# lcd_booster_mk4.net
KiCad netlist of a schematic drawn in EAGLE
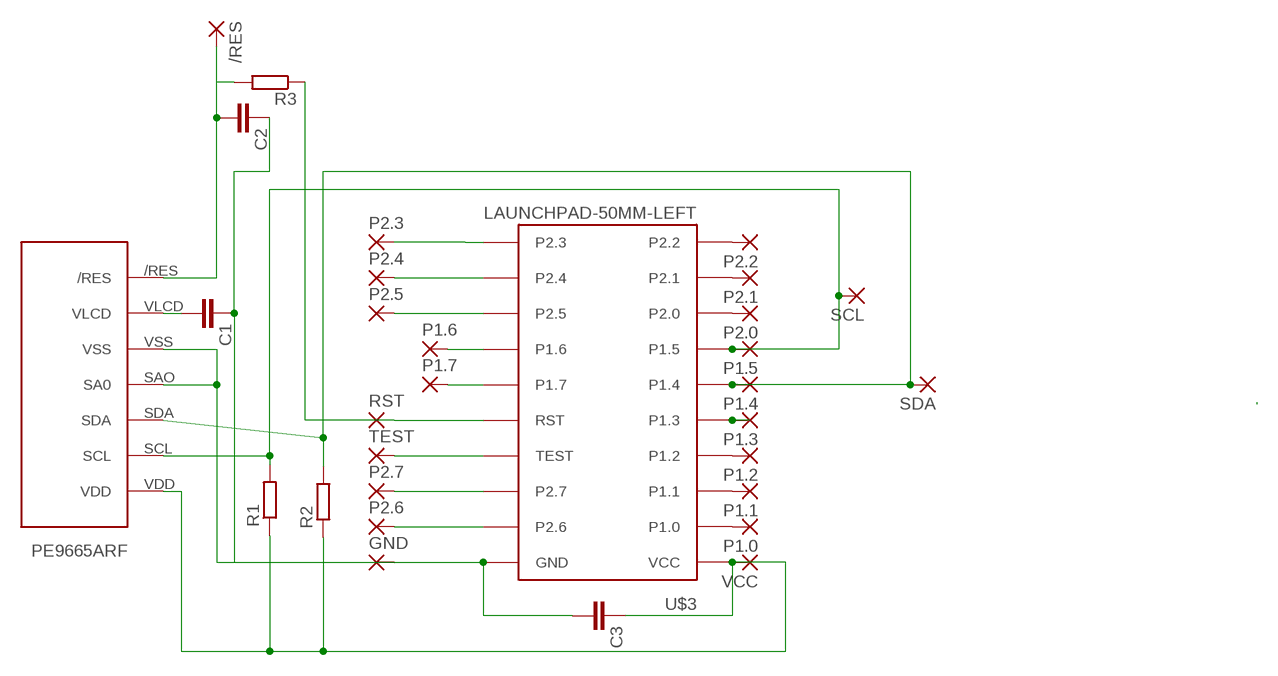
[diagram p0: schematic, sheet 1]

(export (version "E")
  (design (tool "Eeschema 10.0.6"))
  (components
    (comp (ref "/RES")
      (value "1,6/0,9")
      (footprint "eagle-import:1,6_0,9")
      (libsource (lib "eagle-import") (part "1,6/0,9"))
    )
    (comp (ref "C1")
      (value "C-EUC1206")
      (footprint "eagle-import:C1206")
      (libsource (lib "eagle-import") (part "C-EUC1206"))
    )
    (comp (ref "C2")
      (value "C-EUC1206")
      (footprint "eagle-import:C1206")
      (libsource (lib "eagle-import") (part "C-EUC1206"))
    )
    (comp (ref "C3")
      (value "C-EUC1206")
      (footprint "eagle-import:C1206")
      (libsource (lib "eagle-import") (part "C-EUC1206"))
    )
    (comp (ref "GND")
      (value "1,6/0,9")
      (footprint "eagle-import:1,6_0,9")
      (libsource (lib "eagle-import") (part "1,6/0,9"))
    )
    (comp (ref "P1.0")
      (value "1,6/0,9")
      (footprint "eagle-import:1,6_0,9")
      (libsource (lib "eagle-import") (part "1,6/0,9"))
    )
    (comp (ref "P1.1")
      (value "1,6/0,9")
      (footprint "eagle-import:1,6_0,9")
      (libsource (lib "eagle-import") (part "1,6/0,9"))
    )
    (comp (ref "P1.2")
      (value "1,6/0,9")
      (footprint "eagle-import:1,6_0,9")
      (libsource (lib "eagle-import") (part "1,6/0,9"))
    )
    (comp (ref "P1.3")
      (value "1,6/0,9")
      (footprint "eagle-import:1,6_0,9")
      (libsource (lib "eagle-import") (part "1,6/0,9"))
    )
    (comp (ref "P1.4")
      (value "1,6/0,9")
      (footprint "eagle-import:1,6_0,9")
      (libsource (lib "eagle-import") (part "1,6/0,9"))
    )
    (comp (ref "P1.5")
      (value "1,6/0,9")
      (footprint "eagle-import:1,6_0,9")
      (libsource (lib "eagle-import") (part "1,6/0,9"))
    )
    (comp (ref "P1.6")
      (value "1,6/0,9")
      (footprint "eagle-import:1,6_0,9")
      (libsource (lib "eagle-import") (part "1,6/0,9"))
    )
    (comp (ref "P1.7")
      (value "1,6/0,9")
      (footprint "eagle-import:1,6_0,9")
      (libsource (lib "eagle-import") (part "1,6/0,9"))
    )
    (comp (ref "P2.0")
      (value "1,6/0,9")
      (footprint "eagle-import:1,6_0,9")
      (libsource (lib "eagle-import") (part "1,6/0,9"))
    )
    (comp (ref "P2.1")
      (value "SMD2")
      (footprint "eagle-import:SMD1,27-2,54")
      (libsource (lib "eagle-import") (part "SMD2"))
    )
    (comp (ref "P2.2")
      (value "SMD2")
      (footprint "eagle-import:SMD1,27-2,54")
      (libsource (lib "eagle-import") (part "SMD2"))
    )
    (comp (ref "P2.3")
      (value "SMD2")
      (footprint "eagle-import:SMD1,27-2,54")
      (libsource (lib "eagle-import") (part "SMD2"))
    )
    (comp (ref "P2.4")
      (value "SMD2")
      (footprint "eagle-import:SMD1,27-2,54")
      (libsource (lib "eagle-import") (part "SMD2"))
    )
    (comp (ref "P2.5")
      (value "1,6/0,9")
      (footprint "eagle-import:1,6_0,9")
      (libsource (lib "eagle-import") (part "1,6/0,9"))
    )
    (comp (ref "P2.6")
      (value "1,6/0,9")
      (footprint "eagle-import:1,6_0,9")
      (libsource (lib "eagle-import") (part "1,6/0,9"))
    )
    (comp (ref "P2.7")
      (value "1,6/0,9")
      (footprint "eagle-import:1,6_0,9")
      (libsource (lib "eagle-import") (part "1,6/0,9"))
    )
    (comp (ref "R1")
      (value "R-EU_M1206")
      (footprint "eagle-import:M1206")
      (libsource (lib "eagle-import") (part "R-EU_M1206"))
    )
    (comp (ref "R2")
      (value "R-EU_M1206")
      (footprint "eagle-import:M1206")
      (libsource (lib "eagle-import") (part "R-EU_M1206"))
    )
    (comp (ref "R3")
      (value "R-EU_M1206")
      (footprint "eagle-import:M1206")
      (libsource (lib "eagle-import") (part "R-EU_M1206"))
    )
    (comp (ref "RST")
      (value "1,6/0,9")
      (footprint "eagle-import:1,6_0,9")
      (libsource (lib "eagle-import") (part "1,6/0,9"))
    )
    (comp (ref "SCL")
      (value "1,6/0,9")
      (footprint "eagle-import:1,6_0,9")
      (libsource (lib "eagle-import") (part "1,6/0,9"))
    )
    (comp (ref "SDA")
      (value "1,6/0,9")
      (footprint "eagle-import:1,6_0,9")
      (libsource (lib "eagle-import") (part "1,6/0,9"))
    )
    (comp (ref "TEST")
      (value "1,6/0,9")
      (footprint "eagle-import:1,6_0,9")
      (libsource (lib "eagle-import") (part "1,6/0,9"))
    )
    (comp (ref "U$2")
      (value "PE9665ARF")
      (footprint "eagle-import:PE9665ARF")
      (libsource (lib "eagle-import") (part "PE9665ARF"))
    )
    (comp (ref "U$3")
      (value "LAUNCHPAD-50MM-LEFT")
      (footprint "eagle-import:LAUNCHPAD-50MM-LEFT")
      (libsource (lib "eagle-import") (part "LAUNCHPAD-50MM-LEFT"))
    )
    (comp (ref "VCC")
      (value "1,6/0,9")
      (footprint "eagle-import:1,6_0,9")
      (libsource (lib "eagle-import") (part "1,6/0,9"))
    )
  )
  (nets
    (net (code "1") (name "/TEST") (class "Default")
      (node (ref "TEST") (pin "1") (pinfunction "P_1") (pintype "passive"))
      (node (ref "U$3") (pin "TEST") (pinfunction "TEST_TEST") (pintype "bidirectional"))
    )
    (net (code "2") (name "Net-(/RES-P)") (class "Default")
      (node (ref "/RES") (pin "1") (pinfunction "P_1") (pintype "passive"))
      (node (ref "C2") (pin "2") (pinfunction "2_2") (pintype "passive"))
      (node (ref "R3") (pin "2") (pinfunction "2_2") (pintype "passive"))
      (node (ref "U$2") (pin "/RES") (pinfunction "/RES_/RES") (pintype "bidirectional"))
    )
    (net (code "3") (name "Net-(C1-Pad2)") (class "Default")
      (node (ref "C1") (pin "2") (pinfunction "2_2") (pintype "passive"))
      (node (ref "U$2") (pin "VLCD") (pinfunction "VLCD_VLCD") (pintype "bidirectional"))
    )
    (net (code "4") (name "Net-(GND-P)") (class "Default")
      (node (ref "C1") (pin "1") (pinfunction "1_1") (pintype "passive"))
      (node (ref "C2") (pin "1") (pinfunction "1_1") (pintype "passive"))
      (node (ref "C3") (pin "2") (pinfunction "2_2") (pintype "passive"))
      (node (ref "GND") (pin "1") (pinfunction "P_1") (pintype "passive"))
      (node (ref "U$2") (pin "SAO") (pinfunction "SA0_SAO") (pintype "bidirectional"))
      (node (ref "U$2") (pin "VSS") (pinfunction "VSS_VSS") (pintype "power_in"))
      (node (ref "U$3") (pin "GND") (pinfunction "GND_GND") (pintype "power_in"))
    )
    (net (code "5") (name "Net-(P1.0-P)") (class "Default")
      (node (ref "P1.0") (pin "1") (pinfunction "P_1") (pintype "passive"))
      (node (ref "U$3") (pin "P1.0") (pinfunction "P1.0_P1.0") (pintype "bidirectional"))
    )
    (net (code "6") (name "Net-(P1.1-P)") (class "Default")
      (node (ref "P1.1") (pin "1") (pinfunction "P_1") (pintype "passive"))
      (node (ref "U$3") (pin "P1.1") (pinfunction "P1.1_P1.1") (pintype "bidirectional"))
    )
    (net (code "7") (name "Net-(P1.2-P)") (class "Default")
      (node (ref "P1.2") (pin "1") (pinfunction "P_1") (pintype "passive"))
      (node (ref "U$3") (pin "P1.2") (pinfunction "P1.2_P1.2") (pintype "bidirectional"))
    )
    (net (code "8") (name "Net-(P1.3-P)") (class "Default")
      (node (ref "P1.3") (pin "1") (pinfunction "P_1") (pintype "passive"))
      (node (ref "U$3") (pin "P1.3") (pinfunction "P1.3_P1.3") (pintype "bidirectional"))
    )
    (net (code "9") (name "Net-(P1.4-P)") (class "Default")
      (node (ref "P1.4") (pin "1") (pinfunction "P_1") (pintype "passive"))
      (node (ref "R2") (pin "2") (pinfunction "2_2") (pintype "passive"))
      (node (ref "SDA") (pin "1") (pinfunction "P_1") (pintype "passive"))
      (node (ref "U$2") (pin "SDA") (pinfunction "SDA_SDA") (pintype "bidirectional"))
      (node (ref "U$3") (pin "P1.4") (pinfunction "P1.4_P1.4") (pintype "bidirectional"))
    )
    (net (code "10") (name "Net-(P1.5-P)") (class "Default")
      (node (ref "P1.5") (pin "1") (pinfunction "P_1") (pintype "passive"))
      (node (ref "R1") (pin "2") (pinfunction "2_2") (pintype "passive"))
      (node (ref "SCL") (pin "1") (pinfunction "P_1") (pintype "passive"))
      (node (ref "U$2") (pin "SCL") (pinfunction "SCL_SCL") (pintype "bidirectional"))
      (node (ref "U$3") (pin "P1.5") (pinfunction "P1.5_P1.5") (pintype "bidirectional"))
    )
    (net (code "11") (name "Net-(P1.6-P)") (class "Default")
      (node (ref "P1.6") (pin "1") (pinfunction "P_1") (pintype "passive"))
      (node (ref "U$3") (pin "P1.6") (pinfunction "P1.6_P1.6") (pintype "bidirectional"))
    )
    (net (code "12") (name "Net-(P1.7-P)") (class "Default")
      (node (ref "P1.7") (pin "1") (pinfunction "P_1") (pintype "passive"))
      (node (ref "U$3") (pin "P1.7") (pinfunction "P1.7_P1.7") (pintype "bidirectional"))
    )
    (net (code "13") (name "Net-(P2.0-P)") (class "Default")
      (node (ref "P2.0") (pin "1") (pinfunction "P_1") (pintype "passive"))
      (node (ref "U$3") (pin "P2.0") (pinfunction "P2.0_P2.0") (pintype "bidirectional"))
    )
    (net (code "14") (name "Net-(P2.1-P)") (class "Default")
      (node (ref "P2.1") (pin "1") (pinfunction "P_1") (pintype "passive"))
      (node (ref "U$3") (pin "P2.1") (pinfunction "P2.1_P2.1") (pintype "bidirectional"))
    )
    (net (code "15") (name "Net-(P2.2-P)") (class "Default")
      (node (ref "P2.2") (pin "1") (pinfunction "P_1") (pintype "passive"))
      (node (ref "U$3") (pin "P2.2") (pinfunction "P2.2_P2.2") (pintype "bidirectional"))
    )
    (net (code "16") (name "Net-(P2.3-P)") (class "Default")
      (node (ref "P2.3") (pin "1") (pinfunction "P_1") (pintype "passive"))
      (node (ref "U$3") (pin "P2.3") (pinfunction "P2.3_P2.3") (pintype "bidirectional"))
    )
    (net (code "17") (name "Net-(P2.4-P)") (class "Default")
      (node (ref "P2.4") (pin "1") (pinfunction "P_1") (pintype "passive"))
      (node (ref "U$3") (pin "P2.4") (pinfunction "P2.4_P2.4") (pintype "bidirectional"))
    )
    (net (code "18") (name "Net-(P2.5-P)") (class "Default")
      (node (ref "P2.5") (pin "1") (pinfunction "P_1") (pintype "passive"))
      (node (ref "U$3") (pin "P2.5") (pinfunction "P2.5_P2.5") (pintype "bidirectional"))
    )
    (net (code "19") (name "Net-(P2.6-P)") (class "Default")
      (node (ref "P2.6") (pin "1") (pinfunction "P_1") (pintype "passive"))
      (node (ref "U$3") (pin "P2.6") (pinfunction "P2.6_P2.6") (pintype "bidirectional"))
    )
    (net (code "20") (name "Net-(P2.7-P)") (class "Default")
      (node (ref "P2.7") (pin "1") (pinfunction "P_1") (pintype "passive"))
      (node (ref "U$3") (pin "P2.7") (pinfunction "P2.7_P2.7") (pintype "bidirectional"))
    )
    (net (code "21") (name "Net-(RST-P)") (class "Default")
      (node (ref "R3") (pin "1") (pinfunction "1_1") (pintype "passive"))
      (node (ref "RST") (pin "1") (pinfunction "P_1") (pintype "passive"))
      (node (ref "U$3") (pin "RST") (pinfunction "RST_RST") (pintype "bidirectional"))
    )
    (net (code "22") (name "Net-(VCC-P)") (class "Default")
      (node (ref "C3") (pin "1") (pinfunction "1_1") (pintype "passive"))
      (node (ref "R1") (pin "1") (pinfunction "1_1") (pintype "passive"))
      (node (ref "R2") (pin "1") (pinfunction "1_1") (pintype "passive"))
      (node (ref "U$2") (pin "VDD") (pinfunction "VDD_VDD") (pintype "power_in"))
      (node (ref "U$3") (pin "VCC") (pinfunction "VCC_VCC") (pintype "power_in"))
      (node (ref "VCC") (pin "1") (pinfunction "P_1") (pintype "passive"))
    )
  )
)
